# AnalogFrontEnd.net
KiCad netlist of a schematic drawn in Altium Designer
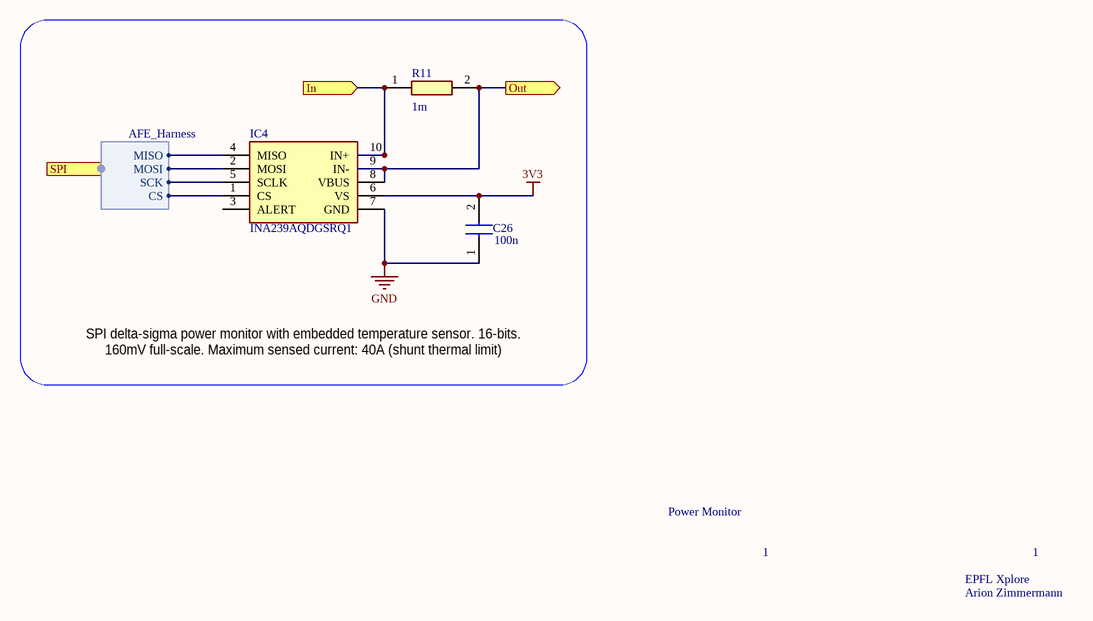
[diagram p0: AnalogFrontEnd.SchDoc]

(export (version "E")
  (design (tool "Eeschema 10.0.6"))
  (components
    (comp (ref "C26")
      (value "100n")
      (footprint "SamacSys:CAPC1608X95N")
      (description "Capacitor")
      (fields
        (field (name "MANUFACTURER_PART_NUMBER") "C0603C104K5RACTU")
        (field (name "MOUSER PART NUMBER") "80-C0603C104K5R")
      )
      (libsource (lib "CarrierBoard") (part "C0603C104K5RACTU"))
    )
    (comp (ref "IC4")
      (value "INA239AQDGSRQ1")
      (footprint "SamacSys:SOP50P490X110-10N")
      (description "Integrated Circuit")
      (fields
        (field (name "MANUFACTURER_PART_NUMBER") "INA229AQDGSRQ1")
        (field (name "MOUSER PART NUMBER") "595-INA229AQDGSRQ1")
      )
      (libsource (lib "*") (part "INA229AQDGSRQ1"))
    )
    (comp (ref "R11")
      (value "1m")
      (footprint "SamacSys:RESC6430X90N")
      (description "Resistor")
      (fields
        (field (name "MANUFACTURER_PART_NUMBER") "PCS2512FR0010ET")
        (field (name "MOUSER PART NUMBER") "588-PCS2512FR0010ET")
      )
      (libsource (lib "SamacSys") (part "PCS2512FR0010ET"))
    )
  )
  (nets
    (net (code "2") (name "/CS") (class "Default")
      (node (ref "IC4") (pin "1") (pinfunction "CS_1") (pintype "passive"))
    )
    (net (code "3") (name "/In") (class "Default")
      (node (ref "IC4") (pin "10") (pinfunction "IN+_10") (pintype "passive"))
      (node (ref "R11") (pin "1") (pinfunction "1_1") (pintype "passive"))
    )
    (net (code "4") (name "/MISO") (class "Default")
      (node (ref "IC4") (pin "4") (pinfunction "MISO_4") (pintype "passive"))
    )
    (net (code "5") (name "/MOSI") (class "Default")
      (node (ref "IC4") (pin "2") (pinfunction "MOSI_2") (pintype "passive"))
    )
    (net (code "6") (name "/Out") (class "Default")
      (node (ref "IC4") (pin "8") (pinfunction "VBUS_8") (pintype "passive"))
      (node (ref "IC4") (pin "9") (pinfunction "IN-_9") (pintype "passive"))
      (node (ref "R11") (pin "2") (pinfunction "2_2") (pintype "passive"))
    )
    (net (code "7") (name "/SCK") (class "Default")
      (node (ref "IC4") (pin "5") (pinfunction "SCLK_5") (pintype "passive"))
    )
    (net (code "9") (name "3V3") (class "Default")
      (node (ref "C26") (pin "2") (pinfunction "2_2") (pintype "passive"))
      (node (ref "IC4") (pin "6") (pinfunction "VS_6") (pintype "passive"))
    )
    (net (code "10") (name "GND") (class "Default")
      (node (ref "C26") (pin "1") (pinfunction "1_1") (pintype "passive"))
      (node (ref "IC4") (pin "7") (pinfunction "GND_7") (pintype "passive"))
    )
    (net (code "11") (name "unconnected-(IC4-ALERT-Pad3)") (class "Default")
      (node (ref "IC4") (pin "3") (pinfunction "ALERT_3") (pintype "passive"))
    )
  )
)
